# Colony.net
KiCad netlist of a schematic drawn in EAGLE
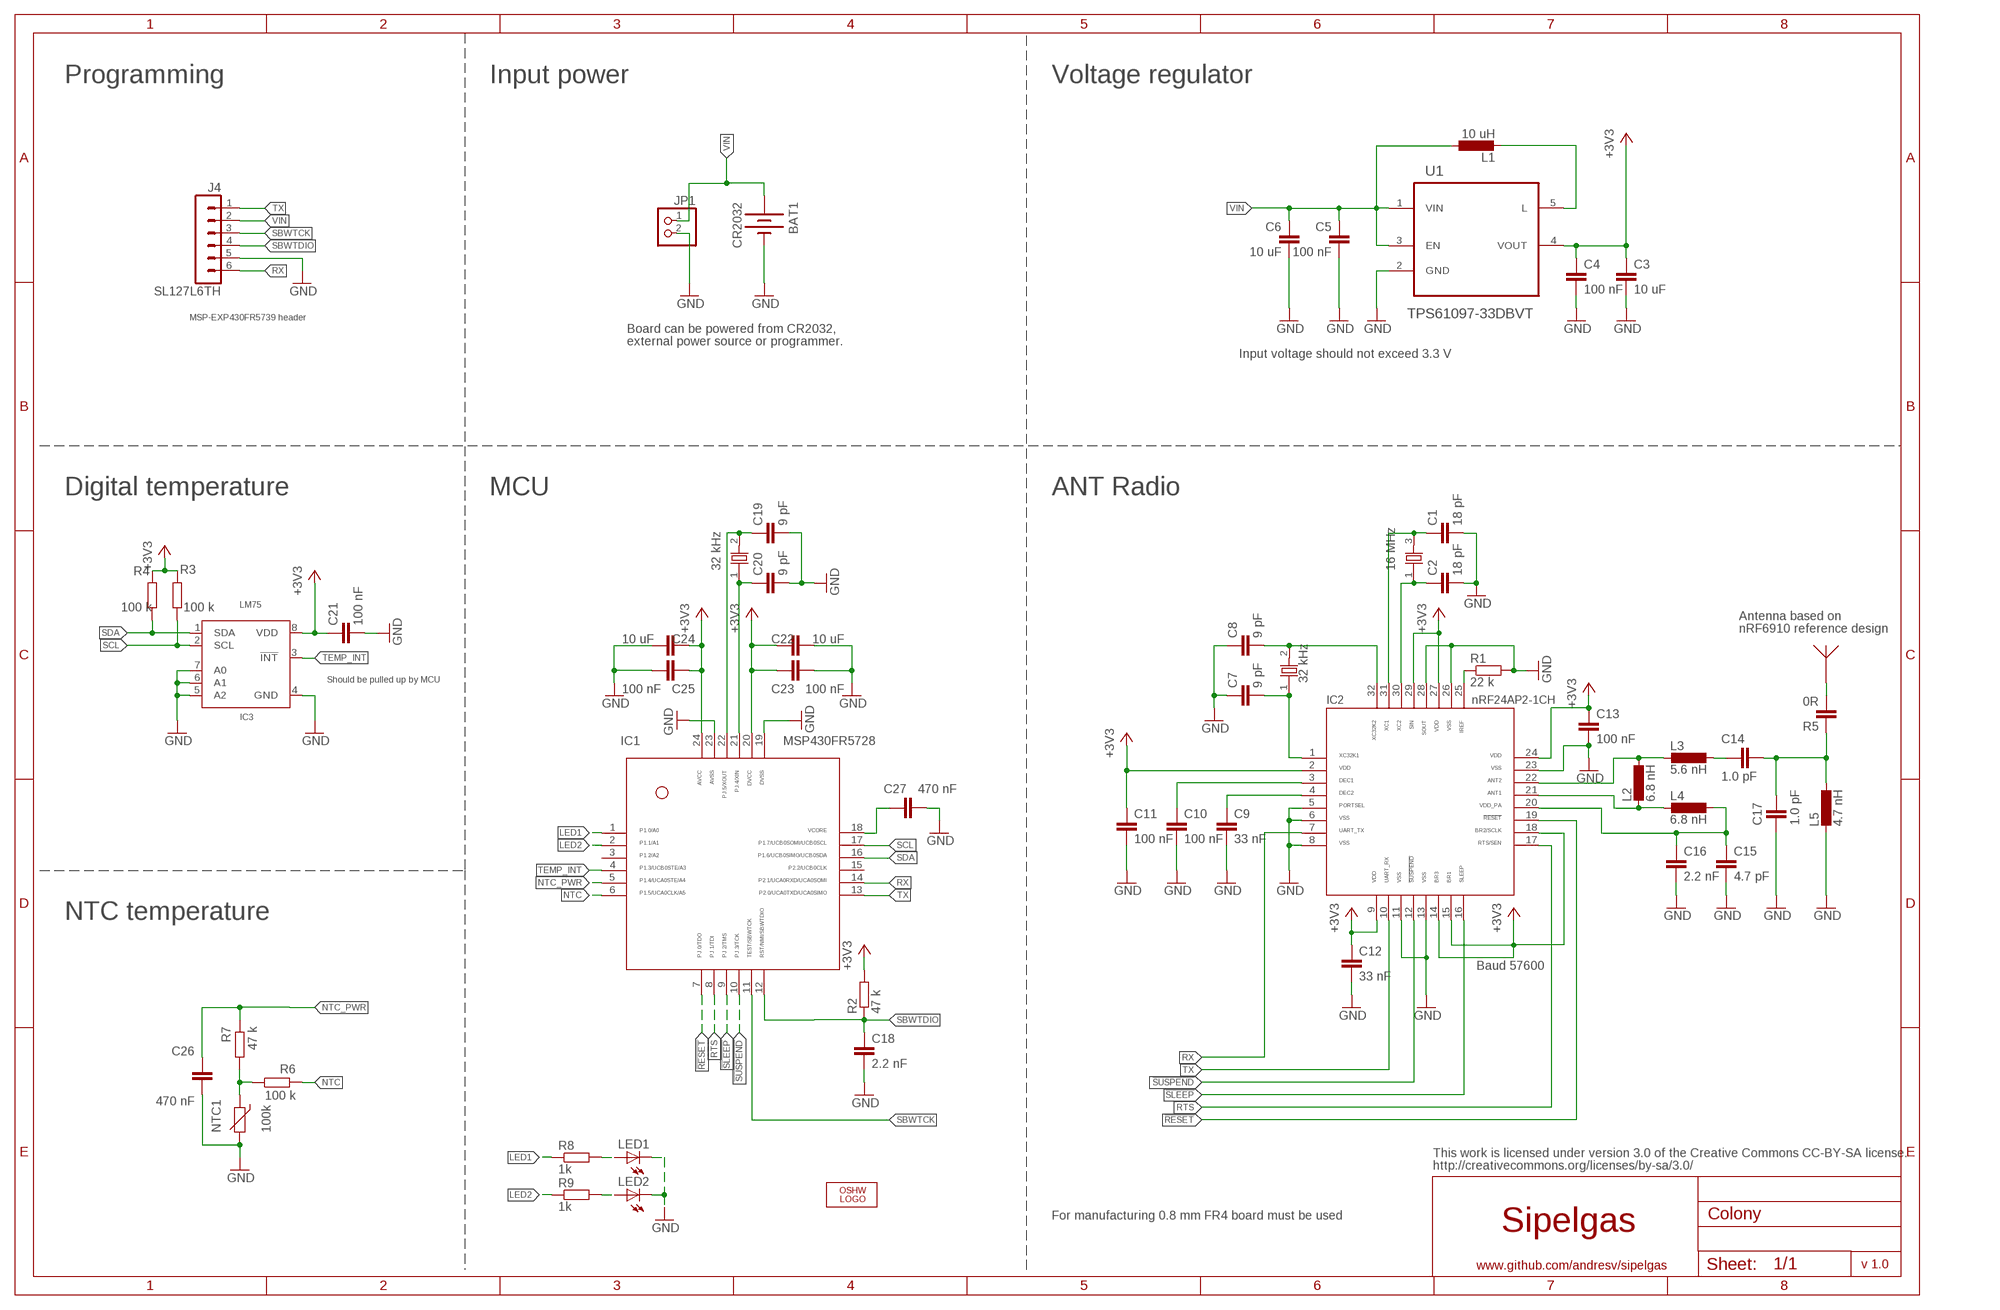
[diagram p0: schematic, sheet 1]

(export (version "E")
  (design (tool "Eeschema 10.0.6"))
  (components
    (comp (ref "BAT1")
      (value "CR2032")
      (footprint "eagle-import:BATTCON_20MM")
      (libsource (lib "eagle-import") (part "LINX-BAT-HLD-00120SMD"))
    )
    (comp (ref "C1")
      (value "18 pF")
      (footprint "eagle-import:C0402")
      (libsource (lib "eagle-import") (part "C-EUC0402"))
    )
    (comp (ref "C2")
      (value "18 pF")
      (footprint "eagle-import:C0402")
      (libsource (lib "eagle-import") (part "C-EUC0402"))
    )
    (comp (ref "C3")
      (value "10 uF")
      (footprint "eagle-import:C0402")
      (libsource (lib "eagle-import") (part "C-EUC0402"))
    )
    (comp (ref "C4")
      (value "100 nF")
      (footprint "eagle-import:C0402")
      (libsource (lib "eagle-import") (part "C-EUC0402"))
    )
    (comp (ref "C5")
      (value "100 nF")
      (footprint "eagle-import:C0402")
      (libsource (lib "eagle-import") (part "C-EUC0402"))
    )
    (comp (ref "C6")
      (value "10 uF")
      (footprint "eagle-import:C0402")
      (libsource (lib "eagle-import") (part "C-EUC0402"))
    )
    (comp (ref "C7")
      (value "9 pF")
      (footprint "eagle-import:C0402")
      (libsource (lib "eagle-import") (part "C-EUC0402"))
    )
    (comp (ref "C8")
      (value "9 pF")
      (footprint "eagle-import:C0402")
      (libsource (lib "eagle-import") (part "C-EUC0402"))
    )
    (comp (ref "C9")
      (value "33 nF")
      (footprint "eagle-import:C0402")
      (libsource (lib "eagle-import") (part "C-EUC0402"))
    )
    (comp (ref "C10")
      (value "100 nF")
      (footprint "eagle-import:C0402")
      (libsource (lib "eagle-import") (part "C-EUC0402"))
    )
    (comp (ref "C11")
      (value "100 nF")
      (footprint "eagle-import:C0402")
      (libsource (lib "eagle-import") (part "C-EUC0402"))
    )
    (comp (ref "C12")
      (value "33 nF")
      (footprint "eagle-import:C0402")
      (libsource (lib "eagle-import") (part "C-EUC0402"))
    )
    (comp (ref "C13")
      (value "100 nF")
      (footprint "eagle-import:C0402")
      (libsource (lib "eagle-import") (part "C-EUC0402"))
    )
    (comp (ref "C14")
      (value "1.0 pF")
      (footprint "eagle-import:C0402")
      (libsource (lib "eagle-import") (part "C-EUC0402"))
    )
    (comp (ref "C15")
      (value "4.7 pF")
      (footprint "eagle-import:C0402")
      (libsource (lib "eagle-import") (part "C-EUC0402"))
    )
    (comp (ref "C16")
      (value "2.2 nF")
      (footprint "eagle-import:C0402")
      (libsource (lib "eagle-import") (part "C-EUC0402"))
    )
    (comp (ref "C17")
      (value "1.0 pF")
      (footprint "eagle-import:C0402")
      (libsource (lib "eagle-import") (part "C-EUC0402"))
    )
    (comp (ref "C18")
      (value "2.2 nF")
      (footprint "eagle-import:C0402")
      (libsource (lib "eagle-import") (part "C-EUC0402"))
    )
    (comp (ref "C19")
      (value "9 pF")
      (footprint "eagle-import:C0402")
      (libsource (lib "eagle-import") (part "C-EUC0402"))
    )
    (comp (ref "C20")
      (value "9 pF")
      (footprint "eagle-import:C0402")
      (libsource (lib "eagle-import") (part "C-EUC0402"))
    )
    (comp (ref "C21")
      (value "100 nF")
      (footprint "eagle-import:C0402")
      (libsource (lib "eagle-import") (part "C-EUC0402"))
    )
    (comp (ref "C22")
      (value "10 uF")
      (footprint "eagle-import:C0402")
      (libsource (lib "eagle-import") (part "C-EUC0402"))
    )
    (comp (ref "C23")
      (value "100 nF")
      (footprint "eagle-import:C0402")
      (libsource (lib "eagle-import") (part "C-EUC0402"))
    )
    (comp (ref "C24")
      (value "10 uF")
      (footprint "eagle-import:C0402")
      (libsource (lib "eagle-import") (part "C-EUC0402"))
    )
    (comp (ref "C25")
      (value "100 nF")
      (footprint "eagle-import:C0402")
      (libsource (lib "eagle-import") (part "C-EUC0402"))
    )
    (comp (ref "C26")
      (value "470 nF")
      (footprint "eagle-import:C0402")
      (libsource (lib "eagle-import") (part "C-EUC0402"))
    )
    (comp (ref "C27")
      (value "470 nF")
      (footprint "eagle-import:C0402")
      (libsource (lib "eagle-import") (part "C-EUC0402"))
    )
    (comp (ref "IC1")
      (value "MSP430FR5728")
      (footprint "eagle-import:QFN-24")
      (libsource (lib "eagle-import") (part "FR57XX--RF24"))
    )
    (comp (ref "IC2")
      (value "nRF24AP2-1CH")
      (footprint "eagle-import:QFN-32")
      (libsource (lib "eagle-import") (part "NRF24AP2"))
    )
    (comp (ref "IC3")
      (value "LM75")
      (footprint "eagle-import:MSOP8")
      (libsource (lib "eagle-import") (part "LM75"))
    )
    (comp (ref "J4")
      (value "SL127L6TH")
      (footprint "eagle-import:SL127L6_MPE")
      (libsource (lib "eagle-import") (part "SL127L6TH"))
    )
    (comp (ref "JP1")
      (value "PINHD-1X2")
      (footprint "eagle-import:1X02")
      (libsource (lib "eagle-import") (part "PINHD-1X2"))
    )
    (comp (ref "L1")
      (value "10 uH")
      (footprint "eagle-import:L0805")
      (libsource (lib "eagle-import") (part "L-EUL0805"))
    )
    (comp (ref "L2")
      (value "6.8 nH")
      (footprint "eagle-import:L0402")
      (libsource (lib "eagle-import") (part "L-EUL0402"))
    )
    (comp (ref "L3")
      (value "5.6 nH")
      (footprint "eagle-import:L0402")
      (libsource (lib "eagle-import") (part "L-EUL0402"))
    )
    (comp (ref "L4")
      (value "6.8 nH")
      (footprint "eagle-import:L0402")
      (libsource (lib "eagle-import") (part "L-EUL0402"))
    )
    (comp (ref "L5")
      (value "4.7 nH")
      (footprint "eagle-import:L0402")
      (libsource (lib "eagle-import") (part "L-EUL0402"))
    )
    (comp (ref "LED1")
      (value "LEDCHIP-LED0603")
      (footprint "eagle-import:CHIP-LED0603")
      (libsource (lib "eagle-import") (part "LEDCHIP-LED0603"))
    )
    (comp (ref "LED2")
      (value "LEDCHIP-LED0603")
      (footprint "eagle-import:CHIP-LED0603")
      (libsource (lib "eagle-import") (part "LEDCHIP-LED0603"))
    )
    (comp (ref "LOGO1")
      (value "OSHW_LOGO_6MILX0100-NT")
      (footprint "eagle-import:OSHW_6X100_NOTEXT")
      (libsource (lib "eagle-import") (part "OSHW_LOGO_6MILX0100-NT"))
    )
    (comp (ref "NTC1")
      (value "100k")
      (footprint "eagle-import:RS-2,5")
      (libsource (lib "eagle-import") (part "THERMISTOR-2,5"))
    )
    (comp (ref "Q1")
      (value "16 MHz")
      (footprint "eagle-import:CTS402_3.2X2.5")
      (libsource (lib "eagle-import") (part "CTS403"))
    )
    (comp (ref "Q2")
      (value "32 kHz")
      (footprint "eagle-import:ABS07")
      (libsource (lib "eagle-import") (part "ABS07"))
    )
    (comp (ref "Q3")
      (value "32 kHz")
      (footprint "eagle-import:ABS07")
      (libsource (lib "eagle-import") (part "ABS07"))
    )
    (comp (ref "R1")
      (value "22 k")
      (footprint "eagle-import:R0402")
      (libsource (lib "eagle-import") (part "R-EU_R0402"))
    )
    (comp (ref "R2")
      (value "47 k")
      (footprint "eagle-import:R0402")
      (libsource (lib "eagle-import") (part "R-EU_R0402"))
    )
    (comp (ref "R3")
      (value "100 k")
      (footprint "eagle-import:R0402")
      (libsource (lib "eagle-import") (part "R-EU_R0402"))
    )
    (comp (ref "R4")
      (value "100 k")
      (footprint "eagle-import:R0402")
      (libsource (lib "eagle-import") (part "R-EU_R0402"))
    )
    (comp (ref "R5")
      (value "0R")
      (footprint "eagle-import:C0201")
      (libsource (lib "eagle-import") (part "C-EUC0201"))
    )
    (comp (ref "R6")
      (value "100 k")
      (footprint "eagle-import:R0402")
      (libsource (lib "eagle-import") (part "R-EU_R0402"))
    )
    (comp (ref "R7")
      (value "47 k")
      (footprint "eagle-import:R0402")
      (libsource (lib "eagle-import") (part "R-EU_R0402"))
    )
    (comp (ref "R8")
      (value "1k")
      (footprint "eagle-import:R0402")
      (libsource (lib "eagle-import") (part "R-EU_R0402"))
    )
    (comp (ref "R9")
      (value "1k")
      (footprint "eagle-import:R0402")
      (libsource (lib "eagle-import") (part "R-EU_R0402"))
    )
    (comp (ref "U$1")
      (value "NRF6910-ANTENNA")
      (footprint "eagle-import:NRF6910")
      (libsource (lib "eagle-import") (part "NRF6910-ANTENNA"))
    )
    (comp (ref "U1")
      (value "TPS61097-33DBVT")
      (footprint "eagle-import:SOT95P280X145-5N")
      (libsource (lib "eagle-import") (part "TPS61097-33DBVT"))
    )
  )
  (nets
    (net (code "1") (name "+3V3") (class "Default")
      (node (ref "C11") (pin "1") (pinfunction "1_1") (pintype "passive"))
      (node (ref "C12") (pin "1") (pinfunction "1_1") (pintype "passive"))
      (node (ref "C13") (pin "1") (pinfunction "1_1") (pintype "passive"))
      (node (ref "C21") (pin "1") (pinfunction "1_1") (pintype "passive"))
      (node (ref "C22") (pin "1") (pinfunction "1_1") (pintype "passive"))
      (node (ref "C23") (pin "1") (pinfunction "1_1") (pintype "passive"))
      (node (ref "C24") (pin "1") (pinfunction "1_1") (pintype "passive"))
      (node (ref "C25") (pin "1") (pinfunction "1_1") (pintype "passive"))
      (node (ref "C3") (pin "1") (pinfunction "1_1") (pintype "passive"))
      (node (ref "C4") (pin "1") (pinfunction "1_1") (pintype "passive"))
      (node (ref "IC1") (pin "20") (pinfunction "20_20") (pintype "passive"))
      (node (ref "IC1") (pin "24") (pinfunction "24_24") (pintype "passive"))
      (node (ref "IC2") (pin "14") (pinfunction "P$14_14") (pintype "bidirectional"))
      (node (ref "IC2") (pin "15") (pinfunction "P$15_15") (pintype "bidirectional"))
      (node (ref "IC2") (pin "18") (pinfunction "P$18_18") (pintype "bidirectional"))
      (node (ref "IC2") (pin "2") (pinfunction "P$2_2") (pintype "bidirectional"))
      (node (ref "IC2") (pin "24") (pinfunction "P$24_24") (pintype "bidirectional"))
      (node (ref "IC2") (pin "27") (pinfunction "P$27_27") (pintype "bidirectional"))
      (node (ref "IC2") (pin "29") (pinfunction "P$29_29") (pintype "bidirectional"))
      (node (ref "IC2") (pin "9") (pinfunction "P$9_9") (pintype "bidirectional"))
      (node (ref "IC3") (pin "8") (pinfunction "VDD_8") (pintype "power_in"))
      (node (ref "R2") (pin "2") (pinfunction "2_2") (pintype "passive"))
      (node (ref "R3") (pin "2") (pinfunction "2_2") (pintype "passive"))
      (node (ref "R4") (pin "2") (pinfunction "2_2") (pintype "passive"))
      (node (ref "U1") (pin "4") (pinfunction "VOUT_4") (pintype "output"))
    )
    (net (code "2") (name "/~{RESET}") (class "Default")
      (node (ref "IC1") (pin "7") (pinfunction "7_7") (pintype "passive"))
      (node (ref "IC2") (pin "19") (pinfunction "P$19_19") (pintype "bidirectional"))
    )
    (net (code "3") (name "/~{SLEEP}") (class "Default")
      (node (ref "IC1") (pin "9") (pinfunction "9_9") (pintype "passive"))
      (node (ref "IC2") (pin "16") (pinfunction "P$16_16") (pintype "bidirectional"))
    )
    (net (code "4") (name "/~{SUSPEND}") (class "Default")
      (node (ref "IC1") (pin "10") (pinfunction "10_10") (pintype "passive"))
      (node (ref "IC2") (pin "12") (pinfunction "P$12_12") (pintype "bidirectional"))
    )
    (net (code "5") (name "GND") (class "Default")
      (node (ref "BAT1") (pin "2") (pinfunction "-_2") (pintype "power_in"))
      (node (ref "C1") (pin "2") (pinfunction "2_2") (pintype "passive"))
      (node (ref "C10") (pin "2") (pinfunction "2_2") (pintype "passive"))
      (node (ref "C11") (pin "2") (pinfunction "2_2") (pintype "passive"))
      (node (ref "C12") (pin "2") (pinfunction "2_2") (pintype "passive"))
      (node (ref "C13") (pin "2") (pinfunction "2_2") (pintype "passive"))
      (node (ref "C15") (pin "2") (pinfunction "2_2") (pintype "passive"))
      (node (ref "C16") (pin "2") (pinfunction "2_2") (pintype "passive"))
      (node (ref "C17") (pin "2") (pinfunction "2_2") (pintype "passive"))
      (node (ref "C18") (pin "2") (pinfunction "2_2") (pintype "passive"))
      (node (ref "C19") (pin "2") (pinfunction "2_2") (pintype "passive"))
      (node (ref "C2") (pin "2") (pinfunction "2_2") (pintype "passive"))
      (node (ref "C20") (pin "2") (pinfunction "2_2") (pintype "passive"))
      (node (ref "C21") (pin "2") (pinfunction "2_2") (pintype "passive"))
      (node (ref "C22") (pin "2") (pinfunction "2_2") (pintype "passive"))
      (node (ref "C23") (pin "2") (pinfunction "2_2") (pintype "passive"))
      (node (ref "C24") (pin "2") (pinfunction "2_2") (pintype "passive"))
      (node (ref "C25") (pin "2") (pinfunction "2_2") (pintype "passive"))
      (node (ref "C26") (pin "2") (pinfunction "2_2") (pintype "passive"))
      (node (ref "C27") (pin "2") (pinfunction "2_2") (pintype "passive"))
      (node (ref "C3") (pin "2") (pinfunction "2_2") (pintype "passive"))
      (node (ref "C4") (pin "2") (pinfunction "2_2") (pintype "passive"))
      (node (ref "C5") (pin "2") (pinfunction "2_2") (pintype "passive"))
      (node (ref "C6") (pin "2") (pinfunction "2_2") (pintype "passive"))
      (node (ref "C7") (pin "1") (pinfunction "1_1") (pintype "passive"))
      (node (ref "C8") (pin "1") (pinfunction "1_1") (pintype "passive"))
      (node (ref "C9") (pin "2") (pinfunction "2_2") (pintype "passive"))
      (node (ref "IC1") (pin "19") (pinfunction "19_19") (pintype "passive"))
      (node (ref "IC1") (pin "23") (pinfunction "23_23") (pintype "passive"))
      (node (ref "IC2") (pin "11") (pinfunction "P$11_11") (pintype "bidirectional"))
      (node (ref "IC2") (pin "13") (pinfunction "P$13_13") (pintype "bidirectional"))
      (node (ref "IC2") (pin "23") (pinfunction "P$23_23") (pintype "bidirectional"))
      (node (ref "IC2") (pin "26") (pinfunction "P$26_26") (pintype "bidirectional"))
      (node (ref "IC2") (pin "28") (pinfunction "P$28_28") (pintype "bidirectional"))
      (node (ref "IC2") (pin "5") (pinfunction "P$5_5") (pintype "bidirectional"))
      (node (ref "IC2") (pin "6") (pinfunction "P$6_6") (pintype "bidirectional"))
      (node (ref "IC2") (pin "8") (pinfunction "P$8_8") (pintype "bidirectional"))
      (node (ref "IC3") (pin "4") (pinfunction "GND_4") (pintype "power_in"))
      (node (ref "IC3") (pin "5") (pinfunction "A2_5") (pintype "bidirectional"))
      (node (ref "IC3") (pin "6") (pinfunction "A1_6") (pintype "bidirectional"))
      (node (ref "IC3") (pin "7") (pinfunction "A0_7") (pintype "bidirectional"))
      (node (ref "J4") (pin "5") (pinfunction "5_5") (pintype "passive"))
      (node (ref "JP1") (pin "2") (pinfunction "2_2") (pintype "passive"))
      (node (ref "L5") (pin "2") (pinfunction "2_2") (pintype "passive"))
      (node (ref "LED1") (pin "C") (pinfunction "C_C") (pintype "passive"))
      (node (ref "LED2") (pin "C") (pinfunction "C_C") (pintype "passive"))
      (node (ref "NTC1") (pin "2") (pinfunction "2_2") (pintype "passive"))
      (node (ref "R1") (pin "2") (pinfunction "2_2") (pintype "passive"))
      (node (ref "U1") (pin "2") (pinfunction "GND_2") (pintype "passive"))
    )
    (net (code "6") (name "LED1") (class "Default")
      (node (ref "IC1") (pin "1") (pinfunction "1_1") (pintype "passive"))
      (node (ref "R8") (pin "1") (pinfunction "1_1") (pintype "passive"))
    )
    (net (code "7") (name "LED2") (class "Default")
      (node (ref "IC1") (pin "2") (pinfunction "2_2") (pintype "passive"))
      (node (ref "R9") (pin "1") (pinfunction "1_1") (pintype "passive"))
    )
    (net (code "8") (name "NTC") (class "Default")
      (node (ref "IC1") (pin "6") (pinfunction "6_6") (pintype "passive"))
      (node (ref "R6") (pin "2") (pinfunction "2_2") (pintype "passive"))
    )
    (net (code "9") (name "NTC_PWR") (class "Default")
      (node (ref "C26") (pin "1") (pinfunction "1_1") (pintype "passive"))
      (node (ref "IC1") (pin "5") (pinfunction "5_5") (pintype "passive"))
      (node (ref "R7") (pin "2") (pinfunction "2_2") (pintype "passive"))
    )
    (net (code "10") (name "Net-(C14-Pad1)") (class "Default")
      (node (ref "C14") (pin "1") (pinfunction "1_1") (pintype "passive"))
      (node (ref "L3") (pin "1") (pinfunction "1_1") (pintype "passive"))
    )
    (net (code "11") (name "Net-(C14-Pad2)") (class "Default")
      (node (ref "C14") (pin "2") (pinfunction "2_2") (pintype "passive"))
      (node (ref "C17") (pin "1") (pinfunction "1_1") (pintype "passive"))
      (node (ref "L5") (pin "1") (pinfunction "1_1") (pintype "passive"))
      (node (ref "R5") (pin "1") (pinfunction "1_1") (pintype "passive"))
    )
    (net (code "12") (name "Net-(C19-Pad1)") (class "Default")
      (node (ref "C19") (pin "1") (pinfunction "1_1") (pintype "passive"))
      (node (ref "IC1") (pin "22") (pinfunction "22_22") (pintype "passive"))
      (node (ref "Q2") (pin "2") (pinfunction "2_2") (pintype "passive"))
    )
    (net (code "13") (name "Net-(C20-Pad1)") (class "Default")
      (node (ref "C20") (pin "1") (pinfunction "1_1") (pintype "passive"))
      (node (ref "IC1") (pin "21") (pinfunction "21_21") (pintype "passive"))
      (node (ref "Q2") (pin "1") (pinfunction "1_1") (pintype "passive"))
    )
    (net (code "14") (name "Net-(C27-Pad1)") (class "Default")
      (node (ref "C27") (pin "1") (pinfunction "1_1") (pintype "passive"))
      (node (ref "IC1") (pin "18") (pinfunction "18_18") (pintype "passive"))
    )
    (net (code "15") (name "Net-(IC2A-P$1)") (class "Default")
      (node (ref "C7") (pin "2") (pinfunction "2_2") (pintype "passive"))
      (node (ref "IC2") (pin "1") (pinfunction "P$1_1") (pintype "bidirectional"))
      (node (ref "Q3") (pin "1") (pinfunction "1_1") (pintype "passive"))
    )
    (net (code "16") (name "Net-(IC2A-P$3)") (class "Default")
      (node (ref "C10") (pin "1") (pinfunction "1_1") (pintype "passive"))
      (node (ref "IC2") (pin "3") (pinfunction "P$3_3") (pintype "bidirectional"))
    )
    (net (code "17") (name "Net-(IC2A-P$4)") (class "Default")
      (node (ref "C9") (pin "1") (pinfunction "1_1") (pintype "passive"))
      (node (ref "IC2") (pin "4") (pinfunction "P$4_4") (pintype "bidirectional"))
    )
    (net (code "18") (name "Net-(IC2A-P$20)") (class "Default")
      (node (ref "C15") (pin "1") (pinfunction "1_1") (pintype "passive"))
      (node (ref "C16") (pin "1") (pinfunction "1_1") (pintype "passive"))
      (node (ref "IC2") (pin "20") (pinfunction "P$20_20") (pintype "bidirectional"))
      (node (ref "L4") (pin "1") (pinfunction "1_1") (pintype "passive"))
    )
    (net (code "19") (name "Net-(IC2A-P$21)") (class "Default")
      (node (ref "IC2") (pin "21") (pinfunction "P$21_21") (pintype "bidirectional"))
      (node (ref "L2") (pin "2") (pinfunction "2_2") (pintype "passive"))
      (node (ref "L4") (pin "2") (pinfunction "2_2") (pintype "passive"))
    )
    (net (code "20") (name "Net-(IC2A-P$22)") (class "Default")
      (node (ref "IC2") (pin "22") (pinfunction "P$22_22") (pintype "bidirectional"))
      (node (ref "L2") (pin "1") (pinfunction "1_1") (pintype "passive"))
      (node (ref "L3") (pin "2") (pinfunction "2_2") (pintype "passive"))
    )
    (net (code "21") (name "Net-(IC2A-P$25)") (class "Default")
      (node (ref "IC2") (pin "25") (pinfunction "P$25_25") (pintype "bidirectional"))
      (node (ref "R1") (pin "1") (pinfunction "1_1") (pintype "passive"))
    )
    (net (code "22") (name "Net-(IC2A-P$30)") (class "Default")
      (node (ref "C2") (pin "1") (pinfunction "1_1") (pintype "passive"))
      (node (ref "IC2") (pin "30") (pinfunction "P$30_30") (pintype "bidirectional"))
      (node (ref "Q1") (pin "1") (pinfunction "1_1") (pintype "passive"))
    )
    (net (code "23") (name "Net-(IC2A-P$31)") (class "Default")
      (node (ref "C1") (pin "1") (pinfunction "1_1") (pintype "passive"))
      (node (ref "IC2") (pin "31") (pinfunction "P$31_31") (pintype "bidirectional"))
      (node (ref "Q1") (pin "3") (pinfunction "2_3") (pintype "passive"))
    )
    (net (code "24") (name "Net-(IC2A-P$32)") (class "Default")
      (node (ref "C8") (pin "2") (pinfunction "2_2") (pintype "passive"))
      (node (ref "IC2") (pin "32") (pinfunction "P$32_32") (pintype "bidirectional"))
      (node (ref "Q3") (pin "2") (pinfunction "2_2") (pintype "passive"))
    )
    (net (code "25") (name "Net-(LED1-PadA)") (class "Default")
      (node (ref "LED1") (pin "A") (pinfunction "A_A") (pintype "passive"))
      (node (ref "R8") (pin "2") (pinfunction "2_2") (pintype "passive"))
    )
    (net (code "26") (name "Net-(LED2-PadA)") (class "Default")
      (node (ref "LED2") (pin "A") (pinfunction "A_A") (pintype "passive"))
      (node (ref "R9") (pin "2") (pinfunction "2_2") (pintype "passive"))
    )
    (net (code "27") (name "Net-(NTC1-Pad1)") (class "Default")
      (node (ref "NTC1") (pin "1") (pinfunction "1_1") (pintype "passive"))
      (node (ref "R6") (pin "1") (pinfunction "1_1") (pintype "passive"))
      (node (ref "R7") (pin "1") (pinfunction "1_1") (pintype "passive"))
    )
    (net (code "28") (name "Net-(U$1-1)") (class "Default")
      (node (ref "R5") (pin "2") (pinfunction "2_2") (pintype "passive"))
      (node (ref "U$1") (pin "P$1") (pinfunction "1_P$1") (pintype "bidirectional"))
    )
    (net (code "29") (name "Net-(U1-L)") (class "Default")
      (node (ref "L1") (pin "2") (pinfunction "2_2") (pintype "passive"))
      (node (ref "U1") (pin "5") (pinfunction "L_5") (pintype "input"))
    )
    (net (code "30") (name "RTS") (class "Default")
      (node (ref "IC1") (pin "8") (pinfunction "8_8") (pintype "passive"))
      (node (ref "IC2") (pin "17") (pinfunction "P$17_17") (pintype "bidirectional"))
    )
    (net (code "31") (name "RX") (class "Default")
      (node (ref "IC1") (pin "14") (pinfunction "14_14") (pintype "passive"))
      (node (ref "IC2") (pin "7") (pinfunction "P$7_7") (pintype "bidirectional"))
      (node (ref "J4") (pin "6") (pinfunction "6_6") (pintype "passive"))
    )
    (net (code "32") (name "SBWTCK") (class "Default")
      (node (ref "IC1") (pin "11") (pinfunction "11_11") (pintype "passive"))
      (node (ref "J4") (pin "3") (pinfunction "3_3") (pintype "passive"))
    )
    (net (code "33") (name "SBWTDIO") (class "Default")
      (node (ref "C18") (pin "1") (pinfunction "1_1") (pintype "passive"))
      (node (ref "IC1") (pin "12") (pinfunction "12_12") (pintype "passive"))
      (node (ref "J4") (pin "4") (pinfunction "4_4") (pintype "passive"))
      (node (ref "R2") (pin "1") (pinfunction "1_1") (pintype "passive"))
    )
    (net (code "34") (name "SCL") (class "Default")
      (node (ref "IC1") (pin "17") (pinfunction "17_17") (pintype "passive"))
      (node (ref "IC3") (pin "2") (pinfunction "SCL_2") (pintype "bidirectional"))
      (node (ref "R3") (pin "1") (pinfunction "1_1") (pintype "passive"))
    )
    (net (code "35") (name "SDA") (class "Default")
      (node (ref "IC1") (pin "16") (pinfunction "16_16") (pintype "passive"))
      (node (ref "IC3") (pin "1") (pinfunction "SDA_1") (pintype "bidirectional"))
      (node (ref "R4") (pin "1") (pinfunction "1_1") (pintype "passive"))
    )
    (net (code "36") (name "TEMP_INT") (class "Default")
      (node (ref "IC1") (pin "4") (pinfunction "4_4") (pintype "passive"))
      (node (ref "IC3") (pin "3") (pinfunction "~{INT}_3") (pintype "bidirectional"))
    )
    (net (code "37") (name "TX") (class "Default")
      (node (ref "IC1") (pin "13") (pinfunction "13_13") (pintype "passive"))
      (node (ref "IC2") (pin "10") (pinfunction "P$10_10") (pintype "bidirectional"))
      (node (ref "J4") (pin "1") (pinfunction "1_1") (pintype "passive"))
    )
    (net (code "38") (name "VIN") (class "Default")
      (node (ref "BAT1") (pin "1") (pinfunction "+_1") (pintype "power_in"))
      (node (ref "C5") (pin "1") (pinfunction "1_1") (pintype "passive"))
      (node (ref "C6") (pin "1") (pinfunction "1_1") (pintype "passive"))
      (node (ref "J4") (pin "2") (pinfunction "2_2") (pintype "passive"))
      (node (ref "JP1") (pin "1") (pinfunction "1_1") (pintype "passive"))
      (node (ref "L1") (pin "1") (pinfunction "1_1") (pintype "passive"))
      (node (ref "U1") (pin "1") (pinfunction "VIN_1") (pintype "power_in"))
      (node (ref "U1") (pin "3") (pinfunction "EN_3") (pintype "input"))
    )
    (net (code "39") (name "unconnected-(IC1-Pad3)") (class "Default")
      (node (ref "IC1") (pin "3") (pinfunction "3_3") (pintype "passive"))
    )
    (net (code "40") (name "unconnected-(IC1-Pad15)") (class "Default")
      (node (ref "IC1") (pin "15") (pinfunction "15_15") (pintype "passive"))
    )
  )
)
